# DIO_MCX.net
KiCad netlist of a schematic drawn in Altium Designer
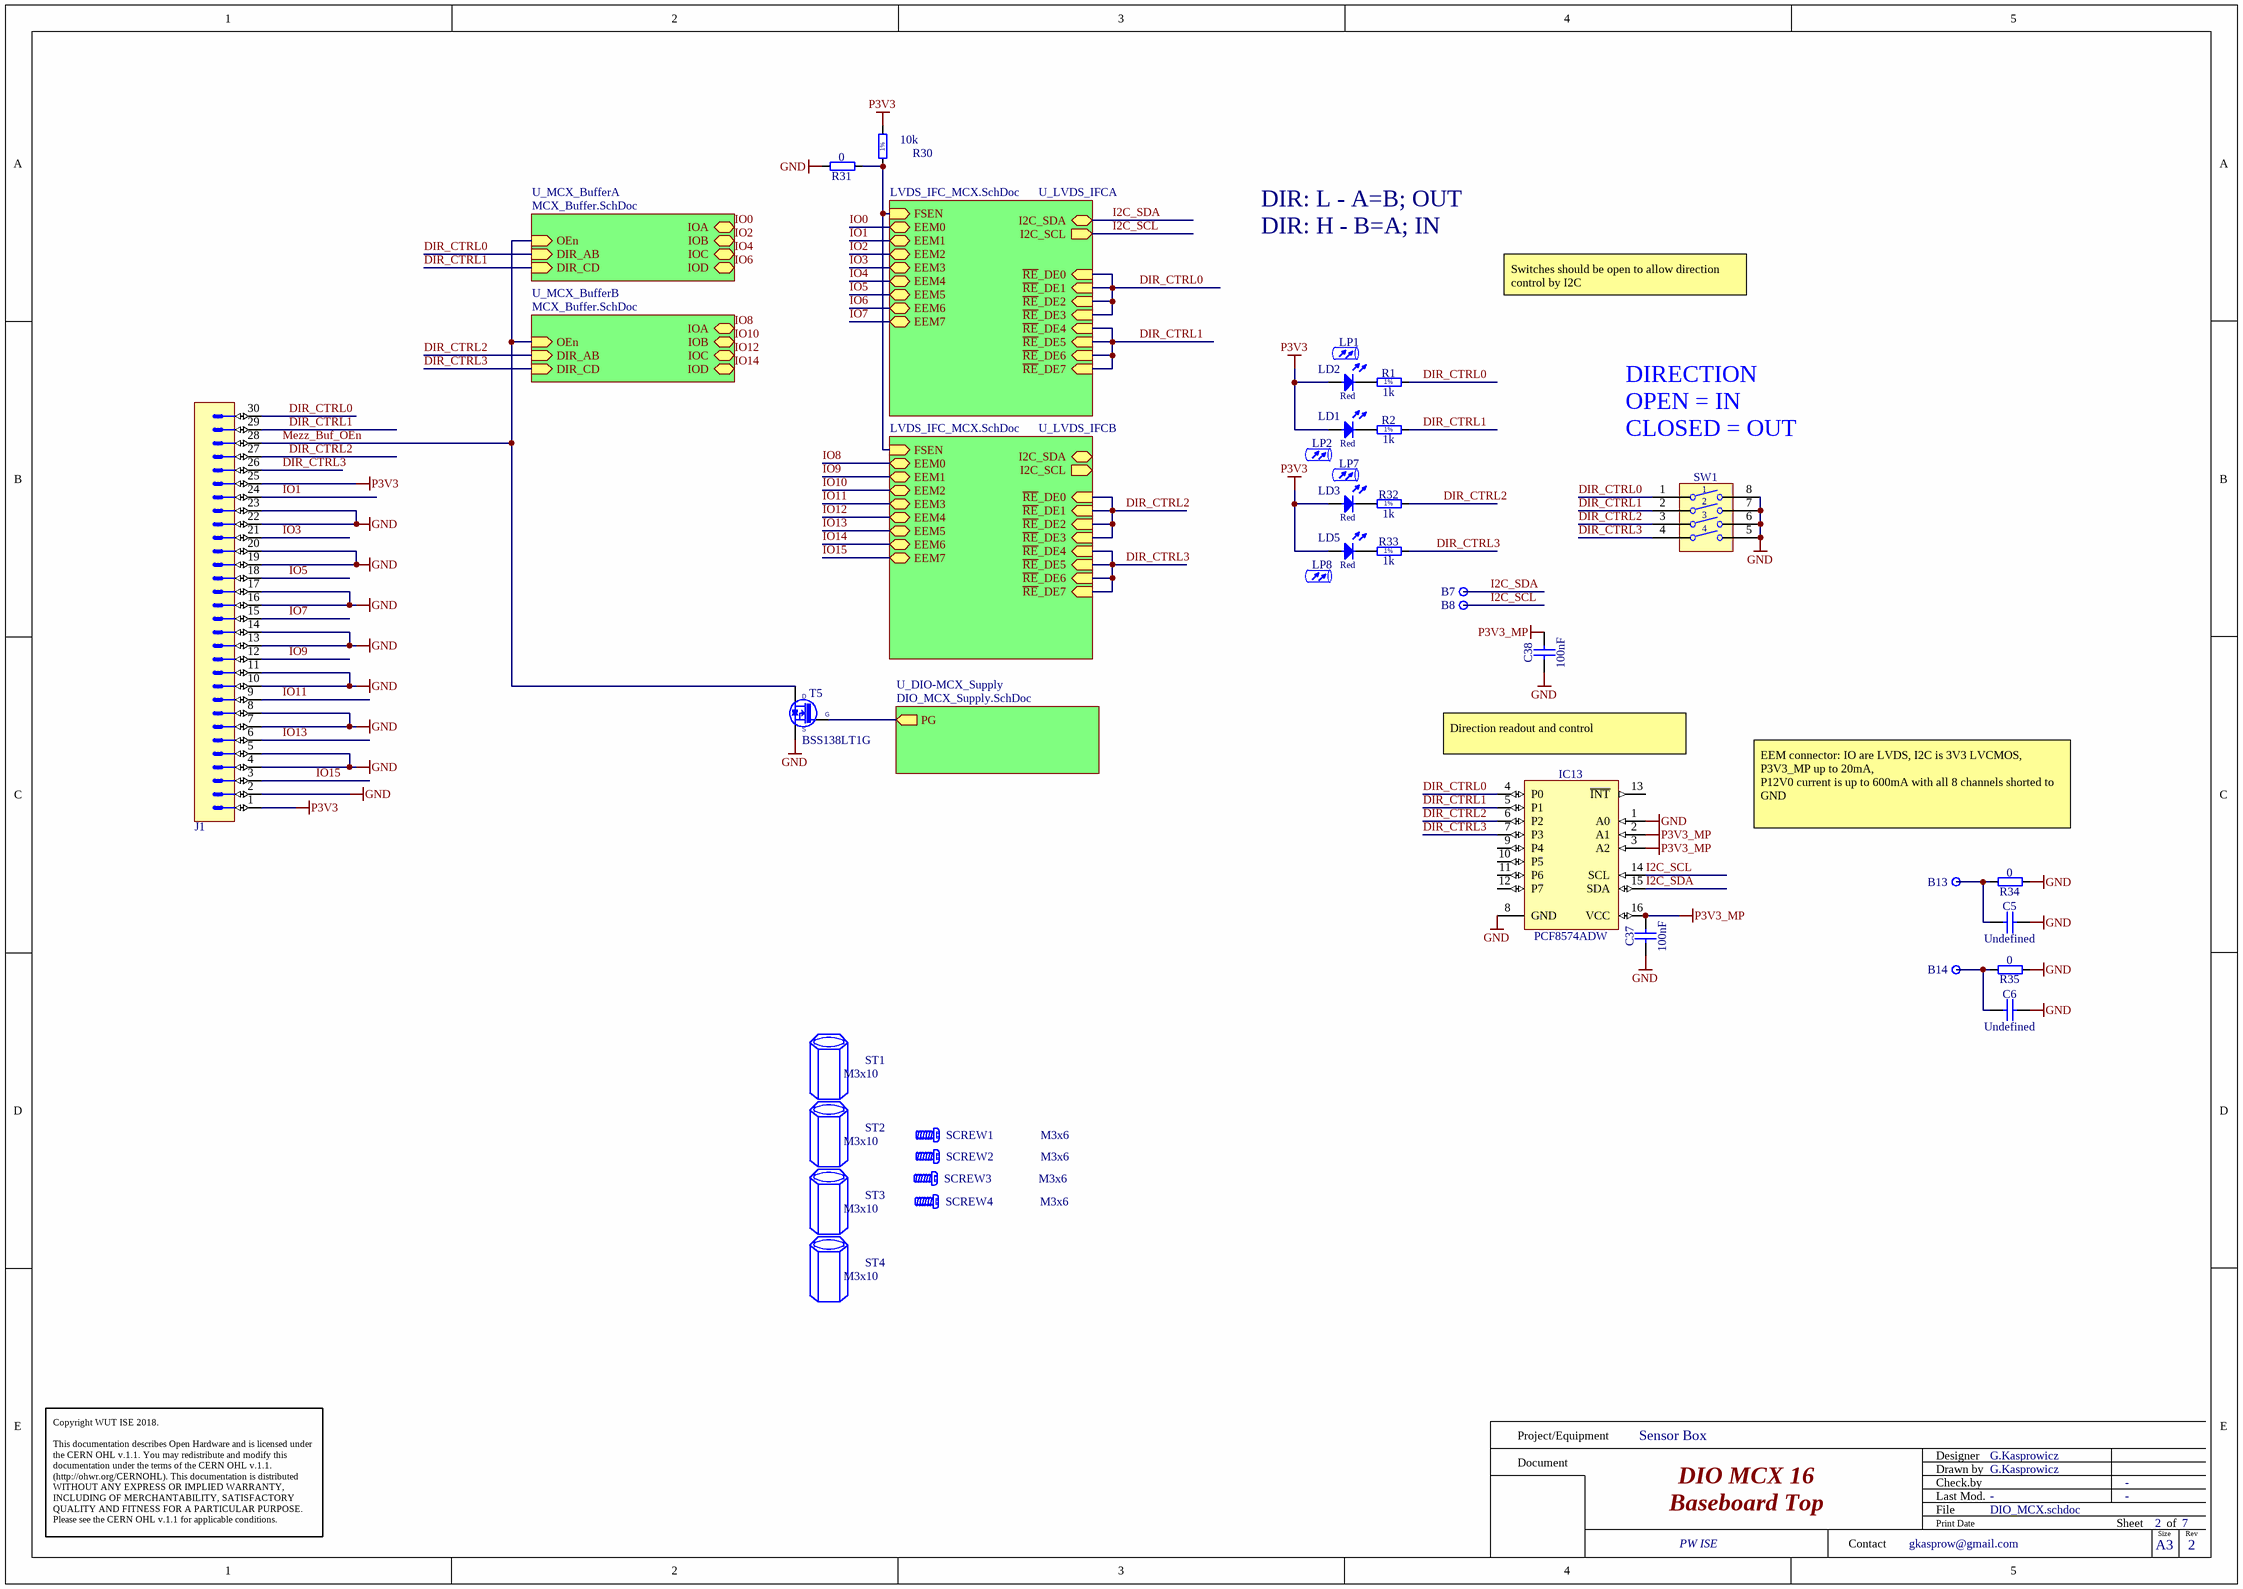
[diagram p0: DIO_MCX.schdoc]

(export (version "E")
  (design (tool "Eeschema 10.0.6"))
  (components
    (comp (ref "B7")
      (value "Plated Hole")
      (footprint "c130h60")
      (description "Single Terminal Socket")
      (fields (field (name "PART NUMBER") "PLATED_HOLE0.6_PAD1.3") (field (name "AUTHOR") "CERN DEM MR"))
      (libsource (lib "Eletro-mechanical") (part "Single Terminal Socket"))
    )
    (comp (ref "B8")
      (value "Plated Hole")
      (footprint "c130h60")
      (description "Single Terminal Socket")
      (fields (field (name "PART NUMBER") "PLATED_HOLE0.6_PAD1.3") (field (name "AUTHOR") "CERN DEM MR"))
      (libsource (lib "Eletro-mechanical") (part "Single Terminal Socket"))
    )
    (comp (ref "B13")
      (value "Plated Hole")
      (footprint "MTG270_500")
      (description "Single Terminal Socket")
      (fields (field (name "PART NUMBER") "PLATED_HOLE2.7_PAD5.0") (field (name "AUTHOR") "CERN DEM JMW"))
      (libsource (lib "Eletro-mechanical") (part "Single Terminal Socket"))
    )
    (comp (ref "B14")
      (value "Plated Hole")
      (footprint "MTG270_500")
      (description "Single Terminal Socket")
      (fields (field (name "PART NUMBER") "PLATED_HOLE2.7_PAD5.0") (field (name "AUTHOR") "CERN DEM JMW"))
      (libsource (lib "Eletro-mechanical") (part "Single Terminal Socket"))
    )
    (comp (ref "C5")
      (value "Undefined")
      (footprint "CAPC2012X135N")
      (description "Non-polarised capacitor")
      (fields (field (name "PART NUMBER") "CC0805_NO-VALUE") (field (name "AUTHOR") "CERN DEM JLC"))
      (libsource (lib "Capacitors") (part "Capacitor - non polarized"))
    )
    (comp (ref "C6")
      (value "Undefined")
      (footprint "CAPC2012X135N")
      (description "Non-polarised capacitor")
      (fields (field (name "PART NUMBER") "CC0805_NO-VALUE") (field (name "AUTHOR") "CERN DEM JLC"))
      (libsource (lib "Capacitors") (part "Capacitor - non polarized"))
    )
    (comp (ref "C37")
      (value "100nF")
      (footprint "CAPC1005X55N")
      (description "Non-polarised capacitor")
      (fields
        (field (name "PART NUMBER") "CC0402_100NF_16V_10%_X5R")
        (field (name "VOLTAGE") "16V")
        (field (name "AUTHOR") "CERN DEM JLC")
      )
      (libsource (lib "Capacitors") (part "Capacitor - non polarized"))
    )
    (comp (ref "C38")
      (value "100nF")
      (footprint "CAPC1005X55N")
      (description "Non-polarised capacitor")
      (fields
        (field (name "PART NUMBER") "CC0402_100NF_16V_10%_X5R")
        (field (name "VOLTAGE") "16V")
        (field (name "AUTHOR") "CERN DEM JLC")
      )
      (libsource (lib "Capacitors") (part "Capacitor - non polarized"))
    )
    (comp (ref "IC13")
      (value "PCF8574ADW")
      (footprint "SOIC127P1030X265-16N")
      (description "Remote 8-bit I/O Expander For I2C Bus")
      (fields (field (name "MANUFACTURER") "TEXAS INSTRUMENTS") (field (name "AUTHOR") "CERN DEM JLC"))
      (libsource (lib "ICs And Semiconductors") (part "PCF8574ADW"))
    )
    (comp (ref "J1")
      (value "~")
      (footprint "3M_N2530-6002RB")
      (description "Connector 30 Male")
      (fields
        (field (name "PART NUMBER") "3M_N2530-6002RB")
        (field (name "MANUFACTURER") "3M")
        (field (name "AUTHOR") "CERN DEM JLC")
      )
      (libsource (lib "Connectors") (part "Connector 30 Male"))
    )
    (comp (ref "LD1")
      (value "Red")
      (footprint "LED_DIALIGHT_551-1107F")
      (description "LED Red 1C 2A")
      (fields
        (field (name "PART NUMBER") "LED_DIALIGHT_551-1107F")
        (field (name "MANUFACTURER") "DIALIGHT")
        (field (name "AUTHOR") "CERN DEM JLC")
      )
      (libsource (lib "ICs And Semiconductors") (part "LED Red 1C 2A"))
    )
    (comp (ref "LD2")
      (value "Red")
      (footprint "LED_DIALIGHT_551-1107F")
      (description "LED Red 1C 2A")
      (fields
        (field (name "PART NUMBER") "LED_DIALIGHT_551-1107F")
        (field (name "MANUFACTURER") "DIALIGHT")
        (field (name "AUTHOR") "CERN DEM JLC")
      )
      (libsource (lib "ICs And Semiconductors") (part "LED Red 1C 2A"))
    )
    (comp (ref "LD3")
      (value "Red")
      (footprint "LED_DIALIGHT_551-1107F")
      (description "LED Red 1C 2A")
      (fields
        (field (name "PART NUMBER") "LED_DIALIGHT_551-1107F")
        (field (name "MANUFACTURER") "DIALIGHT")
        (field (name "AUTHOR") "CERN DEM JLC")
      )
      (libsource (lib "ICs And Semiconductors") (part "LED Red 1C 2A"))
    )
    (comp (ref "LD5")
      (value "Red")
      (footprint "LED_DIALIGHT_551-1107F")
      (description "LED Red 1C 2A")
      (fields
        (field (name "PART NUMBER") "LED_DIALIGHT_551-1107F")
        (field (name "MANUFACTURER") "DIALIGHT")
        (field (name "AUTHOR") "CERN DEM JLC")
      )
      (libsource (lib "ICs And Semiconductors") (part "LED Red 1C 2A"))
    )
    (comp (ref "LP1")
      (value "~")
      (footprint "FIX&FASTEN-LEMB2-8V0-F")
      (description "LED Light_pipe_2.3x8mm")
      (fields
        (field (name "PART NUMBER") "FIX&FASTEN-LEMB2-8V0-F")
        (field (name "MANUFACTURER") "FIX&FASTEN")
        (field (name "AUTHOR") "GK")
      )
      (libsource (lib "LEDs_Displays") (part "LED Light_pipe_2.3x8mm"))
    )
    (comp (ref "LP2")
      (value "~")
      (footprint "FIX&FASTEN-LEMB2-8V0-F")
      (description "LED Light_pipe_2.3x8mm")
      (fields
        (field (name "PART NUMBER") "FIX&FASTEN-LEMB2-8V0-F")
        (field (name "MANUFACTURER") "FIX&FASTEN")
        (field (name "AUTHOR") "GK")
      )
      (libsource (lib "LEDs_Displays") (part "LED Light_pipe_2.3x8mm"))
    )
    (comp (ref "LP7")
      (value "~")
      (footprint "FIX&FASTEN-LEMB2-8V0-F")
      (description "LED Light_pipe_2.3x8mm")
      (fields
        (field (name "PART NUMBER") "FIX&FASTEN-LEMB2-8V0-F")
        (field (name "MANUFACTURER") "FIX&FASTEN")
        (field (name "AUTHOR") "GK")
      )
      (libsource (lib "LEDs_Displays") (part "LED Light_pipe_2.3x8mm"))
    )
    (comp (ref "LP8")
      (value "~")
      (footprint "FIX&FASTEN-LEMB2-8V0-F")
      (description "LED Light_pipe_2.3x8mm")
      (fields
        (field (name "PART NUMBER") "FIX&FASTEN-LEMB2-8V0-F")
        (field (name "MANUFACTURER") "FIX&FASTEN")
        (field (name "AUTHOR") "GK")
      )
      (libsource (lib "LEDs_Displays") (part "LED Light_pipe_2.3x8mm"))
    )
    (comp (ref "R1")
      (value "1k")
      (footprint "RESC1005X40N")
      (description "Resistor - 1%")
      (fields
        (field (name "PART NUMBER") "R0402_1K_1%_0.0625W_100PPM")
        (field (name "POWER") "0.0625W")
        (field (name "AUTHOR") "CERN DEM JLC")
      )
      (libsource (lib "Resistors") (part "Resistor - 1%"))
    )
    (comp (ref "R2")
      (value "1k")
      (footprint "RESC1005X40N")
      (description "Resistor - 1%")
      (fields
        (field (name "PART NUMBER") "R0402_1K_1%_0.0625W_100PPM")
        (field (name "POWER") "0.0625W")
        (field (name "AUTHOR") "CERN DEM JLC")
      )
      (libsource (lib "Resistors") (part "Resistor - 1%"))
    )
    (comp (ref "R30")
      (value "10k")
      (footprint "RESC1005X40N")
      (description "Resistor - 1%")
      (fields
        (field (name "PART NUMBER") "R0402_10K_1%_0.0625W_100PPM")
        (field (name "POWER") "0.0625W")
        (field (name "AUTHOR") "CERN DEM JLC")
      )
      (libsource (lib "Resistors") (part "Resistor - 1%"))
    )
    (comp (ref "R31")
      (value "0")
      (footprint "RESC1608X55N")
      (description "Resistor")
      (fields
        (field (name "PART NUMBER") "R0603_0R_JUMPER")
        (field (name "MANUFACTURER") "GENERIC")
        (field (name "AUTHOR") "CERN DEM JLC")
      )
      (libsource (lib "Resistors") (part "Resistor"))
    )
    (comp (ref "R32")
      (value "1k")
      (footprint "RESC1005X40N")
      (description "Resistor - 1%")
      (fields
        (field (name "PART NUMBER") "R0402_1K_1%_0.0625W_100PPM")
        (field (name "POWER") "0.0625W")
        (field (name "AUTHOR") "CERN DEM JLC")
      )
      (libsource (lib "Resistors") (part "Resistor - 1%"))
    )
    (comp (ref "R33")
      (value "1k")
      (footprint "RESC1005X40N")
      (description "Resistor - 1%")
      (fields
        (field (name "PART NUMBER") "R0402_1K_1%_0.0625W_100PPM")
        (field (name "POWER") "0.0625W")
        (field (name "AUTHOR") "CERN DEM JLC")
      )
      (libsource (lib "Resistors") (part "Resistor - 1%"))
    )
    (comp (ref "R34")
      (value "0")
      (footprint "RESC1608X55N")
      (description "Resistor")
      (fields
        (field (name "PART NUMBER") "R0603_0R_JUMPER")
        (field (name "MANUFACTURER") "GENERIC")
        (field (name "AUTHOR") "CERN DEM JLC")
      )
      (libsource (lib "Resistors") (part "Resistor"))
    )
    (comp (ref "R35")
      (value "0")
      (footprint "RESC1608X55N")
      (description "Resistor")
      (fields
        (field (name "PART NUMBER") "R0603_0R_JUMPER")
        (field (name "MANUFACTURER") "GENERIC")
        (field (name "AUTHOR") "CERN DEM JLC")
      )
      (libsource (lib "Resistors") (part "Resistor"))
    )
    (comp (ref "SCREW1")
      (value "M3x6")
      (footprint "BOSSARD_BN5687-3061605_v")
      (description "Screw")
      (fields
        (field (name "PART NUMBER") "BOSSARD_BN5687-3061605_v")
        (field (name "MANUFACTURER") "BOSSARD")
        (field (name "AUTHOR") "CERN DEM JLC")
      )
      (libsource (lib "Eletro-mechanical") (part "Screw"))
    )
    (comp (ref "SCREW2")
      (value "M3x6")
      (footprint "BOSSARD_BN5687-3061605_v")
      (description "Screw")
      (fields
        (field (name "PART NUMBER") "BOSSARD_BN5687-3061605_v")
        (field (name "MANUFACTURER") "BOSSARD")
        (field (name "AUTHOR") "CERN DEM JLC")
      )
      (libsource (lib "Eletro-mechanical") (part "Screw"))
    )
    (comp (ref "SCREW3")
      (value "M3x6")
      (footprint "BOSSARD_BN5687-3061605_v")
      (description "Screw")
      (fields
        (field (name "PART NUMBER") "BOSSARD_BN5687-3061605_v")
        (field (name "MANUFACTURER") "BOSSARD")
        (field (name "AUTHOR") "CERN DEM JLC")
      )
      (libsource (lib "Eletro-mechanical") (part "Screw"))
    )
    (comp (ref "SCREW4")
      (value "M3x6")
      (footprint "BOSSARD_BN5687-3061605_v")
      (description "Screw")
      (fields
        (field (name "PART NUMBER") "BOSSARD_BN5687-3061605_v")
        (field (name "MANUFACTURER") "BOSSARD")
        (field (name "AUTHOR") "CERN DEM JLC")
      )
      (libsource (lib "Eletro-mechanical") (part "Screw"))
    )
    (comp (ref "ST1")
      (value "M3x10")
      (footprint "HARWIN_R25-1001002")
      (description "M3x10 standoff")
      (fields
        (field (name "PART NUMBER") "DREMEC_TFF-M3X10/DR124")
        (field (name "MANUFACTURER") "DREMEC")
        (field (name "AUTHOR") "GK")
      )
      (libsource (lib "Mechanical") (part "MECH_Standoff_M3x10"))
    )
    (comp (ref "ST2")
      (value "M3x10")
      (footprint "HARWIN_R25-1001002")
      (description "M3x10 standoff")
      (fields
        (field (name "PART NUMBER") "DREMEC_TFF-M3X10/DR124")
        (field (name "MANUFACTURER") "DREMEC")
        (field (name "AUTHOR") "GK")
      )
      (libsource (lib "Mechanical") (part "MECH_Standoff_M3x10"))
    )
    (comp (ref "ST3")
      (value "M3x10")
      (footprint "HARWIN_R25-1001002")
      (description "M3x10 standoff")
      (fields
        (field (name "PART NUMBER") "DREMEC_TFF-M3X10/DR124")
        (field (name "MANUFACTURER") "DREMEC")
        (field (name "AUTHOR") "GK")
      )
      (libsource (lib "Mechanical") (part "MECH_Standoff_M3x10"))
    )
    (comp (ref "ST4")
      (value "M3x10")
      (footprint "HARWIN_R25-1001002")
      (description "M3x10 standoff")
      (fields
        (field (name "PART NUMBER") "DREMEC_TFF-M3X10/DR124")
        (field (name "MANUFACTURER") "DREMEC")
        (field (name "AUTHOR") "GK")
      )
      (libsource (lib "Mechanical") (part "MECH_Standoff_M3x10"))
    )
    (comp (ref "SW1")
      (value "Switch")
      (footprint "SW_OMRON_A6S-4102-H")
      (description "4 Ways SPST DIP Switch")
      (fields
        (field (name "PART NUMBER") "SW_OMRON_A6S-4102-H")
        (field (name "MANUFACTURER") "OMRON")
        (field (name "AUTHOR") "CERN DEM JMW")
      )
      (libsource (lib "Eletro-mechanical") (part "SW 4x SPST DIP Switch"))
    )
    (comp (ref "T5")
      (value "BSS138LT1G")
      (footprint "SOT95P240X110-3N")
      (description "N-CHANNEL MOSFET WITH DIODE")
      (fields (field (name "MANUFACTURER") "ON SEMICONDUCTOR") (field (name "AUTHOR") "CERN DEM JLC"))
      (libsource (lib "ICs And Semiconductors") (part "N-MOSFET-D 1G 2S 3D"))
    )
  )
  (nets
    (net (code "1") (name "/DIR_CTRL0") (class "Default")
      (node (ref "IC13") (pin "4") (pinfunction "P0_4") (pintype "bidirectional"))
      (node (ref "J1") (pin "30") (pinfunction "30_30") (pintype "bidirectional"))
      (node (ref "R1") (pin "2") (pinfunction "2_2") (pintype "passive"))
      (node (ref "SW1") (pin "1") (pinfunction "1_1") (pintype "passive"))
    )
    (net (code "2") (name "/DIR_CTRL1") (class "Default")
      (node (ref "IC13") (pin "5") (pinfunction "P1_5") (pintype "bidirectional"))
      (node (ref "J1") (pin "29") (pinfunction "29_29") (pintype "bidirectional"))
      (node (ref "R2") (pin "2") (pinfunction "2_2") (pintype "passive"))
      (node (ref "SW1") (pin "2") (pinfunction "2_2") (pintype "passive"))
    )
    (net (code "3") (name "/DIR_CTRL2") (class "Default")
      (node (ref "IC13") (pin "6") (pinfunction "P2_6") (pintype "bidirectional"))
      (node (ref "J1") (pin "27") (pinfunction "27_27") (pintype "bidirectional"))
      (node (ref "R32") (pin "2") (pinfunction "2_2") (pintype "passive"))
      (node (ref "SW1") (pin "3") (pinfunction "3_3") (pintype "passive"))
    )
    (net (code "4") (name "/DIR_CTRL3") (class "Default")
      (node (ref "IC13") (pin "7") (pinfunction "P3_7") (pintype "bidirectional"))
      (node (ref "J1") (pin "26") (pinfunction "26_26") (pintype "bidirectional"))
      (node (ref "R33") (pin "2") (pinfunction "2_2") (pintype "passive"))
      (node (ref "SW1") (pin "4") (pinfunction "4_4") (pintype "passive"))
    )
    (net (code "5") (name "/FSEN") (class "Default")
      (node (ref "R30") (pin "1") (pinfunction "1_1") (pintype "passive"))
      (node (ref "R31") (pin "1") (pinfunction "1_1") (pintype "passive"))
    )
    (net (code "6") (name "/I2C_SCL") (class "Default")
      (node (ref "B8") (pin "1") (pinfunction "1_1") (pintype "bidirectional"))
      (node (ref "IC13") (pin "14") (pinfunction "SCL_14") (pintype "input"))
    )
    (net (code "8") (name "/I2C_SDA") (class "Default")
      (node (ref "B7") (pin "1") (pinfunction "1_1") (pintype "bidirectional"))
      (node (ref "IC13") (pin "15") (pinfunction "SDA_15") (pintype "bidirectional"))
    )
    (net (code "11") (name "/IO1") (class "Default")
      (node (ref "J1") (pin "24") (pinfunction "24_24") (pintype "bidirectional"))
    )
    (net (code "13") (name "/IO3") (class "Default")
      (node (ref "J1") (pin "21") (pinfunction "21_21") (pintype "bidirectional"))
    )
    (net (code "15") (name "/IO5") (class "Default")
      (node (ref "J1") (pin "18") (pinfunction "18_18") (pintype "bidirectional"))
    )
    (net (code "17") (name "/IO7") (class "Default")
      (node (ref "J1") (pin "15") (pinfunction "15_15") (pintype "bidirectional"))
    )
    (net (code "19") (name "/IO9") (class "Default")
      (node (ref "J1") (pin "12") (pinfunction "12_12") (pintype "bidirectional"))
    )
    (net (code "21") (name "/IO11") (class "Default")
      (node (ref "J1") (pin "9") (pinfunction "9_9") (pintype "bidirectional"))
    )
    (net (code "23") (name "/IO13") (class "Default")
      (node (ref "J1") (pin "6") (pinfunction "6_6") (pintype "bidirectional"))
    )
    (net (code "25") (name "/IO15") (class "Default")
      (node (ref "J1") (pin "3") (pinfunction "3_3") (pintype "bidirectional"))
    )
    (net (code "26") (name "/Mezz_Buf_OEn") (class "Default")
      (node (ref "J1") (pin "28") (pinfunction "28_28") (pintype "bidirectional"))
      (node (ref "T5") (pin "3") (pinfunction "D_3") (pintype "passive"))
    )
    (net (code "27") (name "/PG") (class "Default")
      (node (ref "T5") (pin "1") (pinfunction "G_1") (pintype "passive"))
    )
    (net (code "28") (name "GND") (class "Default")
      (node (ref "C37") (pin "1") (pinfunction "1_1") (pintype "passive"))
      (node (ref "C38") (pin "1") (pinfunction "1_1") (pintype "passive"))
      (node (ref "C5") (pin "2") (pinfunction "2_2") (pintype "passive"))
      (node (ref "C6") (pin "2") (pinfunction "2_2") (pintype "passive"))
      (node (ref "IC13") (pin "1") (pinfunction "A0_1") (pintype "input"))
      (node (ref "IC13") (pin "8") (pinfunction "GND_8") (pintype "power_in"))
      (node (ref "J1") (pin "10") (pinfunction "10_10") (pintype "bidirectional"))
      (node (ref "J1") (pin "11") (pinfunction "11_11") (pintype "bidirectional"))
      (node (ref "J1") (pin "13") (pinfunction "13_13") (pintype "bidirectional"))
      (node (ref "J1") (pin "14") (pinfunction "14_14") (pintype "bidirectional"))
      (node (ref "J1") (pin "16") (pinfunction "16_16") (pintype "bidirectional"))
      (node (ref "J1") (pin "17") (pinfunction "17_17") (pintype "bidirectional"))
      (node (ref "J1") (pin "19") (pinfunction "19_19") (pintype "bidirectional"))
      (node (ref "J1") (pin "2") (pinfunction "2_2") (pintype "bidirectional"))
      (node (ref "J1") (pin "20") (pinfunction "20_20") (pintype "bidirectional"))
      (node (ref "J1") (pin "22") (pinfunction "22_22") (pintype "bidirectional"))
      (node (ref "J1") (pin "23") (pinfunction "23_23") (pintype "bidirectional"))
      (node (ref "J1") (pin "4") (pinfunction "4_4") (pintype "bidirectional"))
      (node (ref "J1") (pin "5") (pinfunction "5_5") (pintype "bidirectional"))
      (node (ref "J1") (pin "7") (pinfunction "7_7") (pintype "bidirectional"))
      (node (ref "J1") (pin "8") (pinfunction "8_8") (pintype "bidirectional"))
      (node (ref "R31") (pin "2") (pinfunction "2_2") (pintype "passive"))
      (node (ref "R34") (pin "1") (pinfunction "1_1") (pintype "passive"))
      (node (ref "R35") (pin "1") (pinfunction "1_1") (pintype "passive"))
      (node (ref "SW1") (pin "5") (pinfunction "5_5") (pintype "passive"))
      (node (ref "SW1") (pin "6") (pinfunction "6_6") (pintype "passive"))
      (node (ref "SW1") (pin "7") (pinfunction "7_7") (pintype "passive"))
      (node (ref "SW1") (pin "8") (pinfunction "8_8") (pintype "passive"))
      (node (ref "T5") (pin "2") (pinfunction "S_2") (pintype "passive"))
    )
    (net (code "29") (name "Net-(B13-Pad1)") (class "Default")
      (node (ref "B13") (pin "1") (pinfunction "1_1") (pintype "bidirectional"))
      (node (ref "C5") (pin "1") (pinfunction "1_1") (pintype "passive"))
      (node (ref "R34") (pin "2") (pinfunction "2_2") (pintype "passive"))
    )
    (net (code "30") (name "Net-(B14-Pad1)") (class "Default")
      (node (ref "B14") (pin "1") (pinfunction "1_1") (pintype "bidirectional"))
      (node (ref "C6") (pin "1") (pinfunction "1_1") (pintype "passive"))
      (node (ref "R35") (pin "2") (pinfunction "2_2") (pintype "passive"))
    )
    (net (code "31") (name "Net-(LD1-C)") (class "Default")
      (node (ref "LD1") (pin "1") (pinfunction "C_1") (pintype "passive"))
      (node (ref "R2") (pin "1") (pinfunction "1_1") (pintype "passive"))
    )
    (net (code "32") (name "Net-(LD2-C)") (class "Default")
      (node (ref "LD2") (pin "1") (pinfunction "C_1") (pintype "passive"))
      (node (ref "R1") (pin "1") (pinfunction "1_1") (pintype "passive"))
    )
    (net (code "33") (name "Net-(LD3-C)") (class "Default")
      (node (ref "LD3") (pin "1") (pinfunction "C_1") (pintype "passive"))
      (node (ref "R32") (pin "1") (pinfunction "1_1") (pintype "passive"))
    )
    (net (code "34") (name "Net-(LD5-C)") (class "Default")
      (node (ref "LD5") (pin "1") (pinfunction "C_1") (pintype "passive"))
      (node (ref "R33") (pin "1") (pinfunction "1_1") (pintype "passive"))
    )
    (net (code "35") (name "P3V3") (class "Default")
      (node (ref "J1") (pin "1") (pinfunction "1_1") (pintype "bidirectional"))
      (node (ref "J1") (pin "25") (pinfunction "25_25") (pintype "bidirectional"))
      (node (ref "LD1") (pin "2") (pinfunction "A_2") (pintype "passive"))
      (node (ref "LD2") (pin "2") (pinfunction "A_2") (pintype "passive"))
      (node (ref "LD3") (pin "2") (pinfunction "A_2") (pintype "passive"))
      (node (ref "LD5") (pin "2") (pinfunction "A_2") (pintype "passive"))
      (node (ref "R30") (pin "2") (pinfunction "2_2") (pintype "passive"))
    )
    (net (code "36") (name "P3V3_MP") (class "Default")
      (node (ref "C37") (pin "2") (pinfunction "2_2") (pintype "passive"))
      (node (ref "C38") (pin "2") (pinfunction "2_2") (pintype "passive"))
      (node (ref "IC13") (pin "16") (pinfunction "VCC_16") (pintype "bidirectional"))
      (node (ref "IC13") (pin "2") (pinfunction "A1_2") (pintype "input"))
      (node (ref "IC13") (pin "3") (pinfunction "A2_3") (pintype "input"))
    )
    (net (code "37") (name "unconnected-(IC13-P4-Pad9)") (class "Default")
      (node (ref "IC13") (pin "9") (pinfunction "P4_9") (pintype "bidirectional"))
    )
    (net (code "38") (name "unconnected-(IC13-P5-Pad10)") (class "Default")
      (node (ref "IC13") (pin "10") (pinfunction "P5_10") (pintype "bidirectional"))
    )
    (net (code "39") (name "unconnected-(IC13-P6-Pad11)") (class "Default")
      (node (ref "IC13") (pin "11") (pinfunction "P6_11") (pintype "bidirectional"))
    )
    (net (code "40") (name "unconnected-(IC13-P7-Pad12)") (class "Default")
      (node (ref "IC13") (pin "12") (pinfunction "P7_12") (pintype "bidirectional"))
    )
    (net (code "41") (name "unconnected-(IC13-~{INT}-Pad13)") (class "Default")
      (node (ref "IC13") (pin "13") (pinfunction "~{INT}_13") (pintype "output"))
    )
  )
)
